# avbrd.net
KiCad netlist of a schematic drawn in Altium Designer
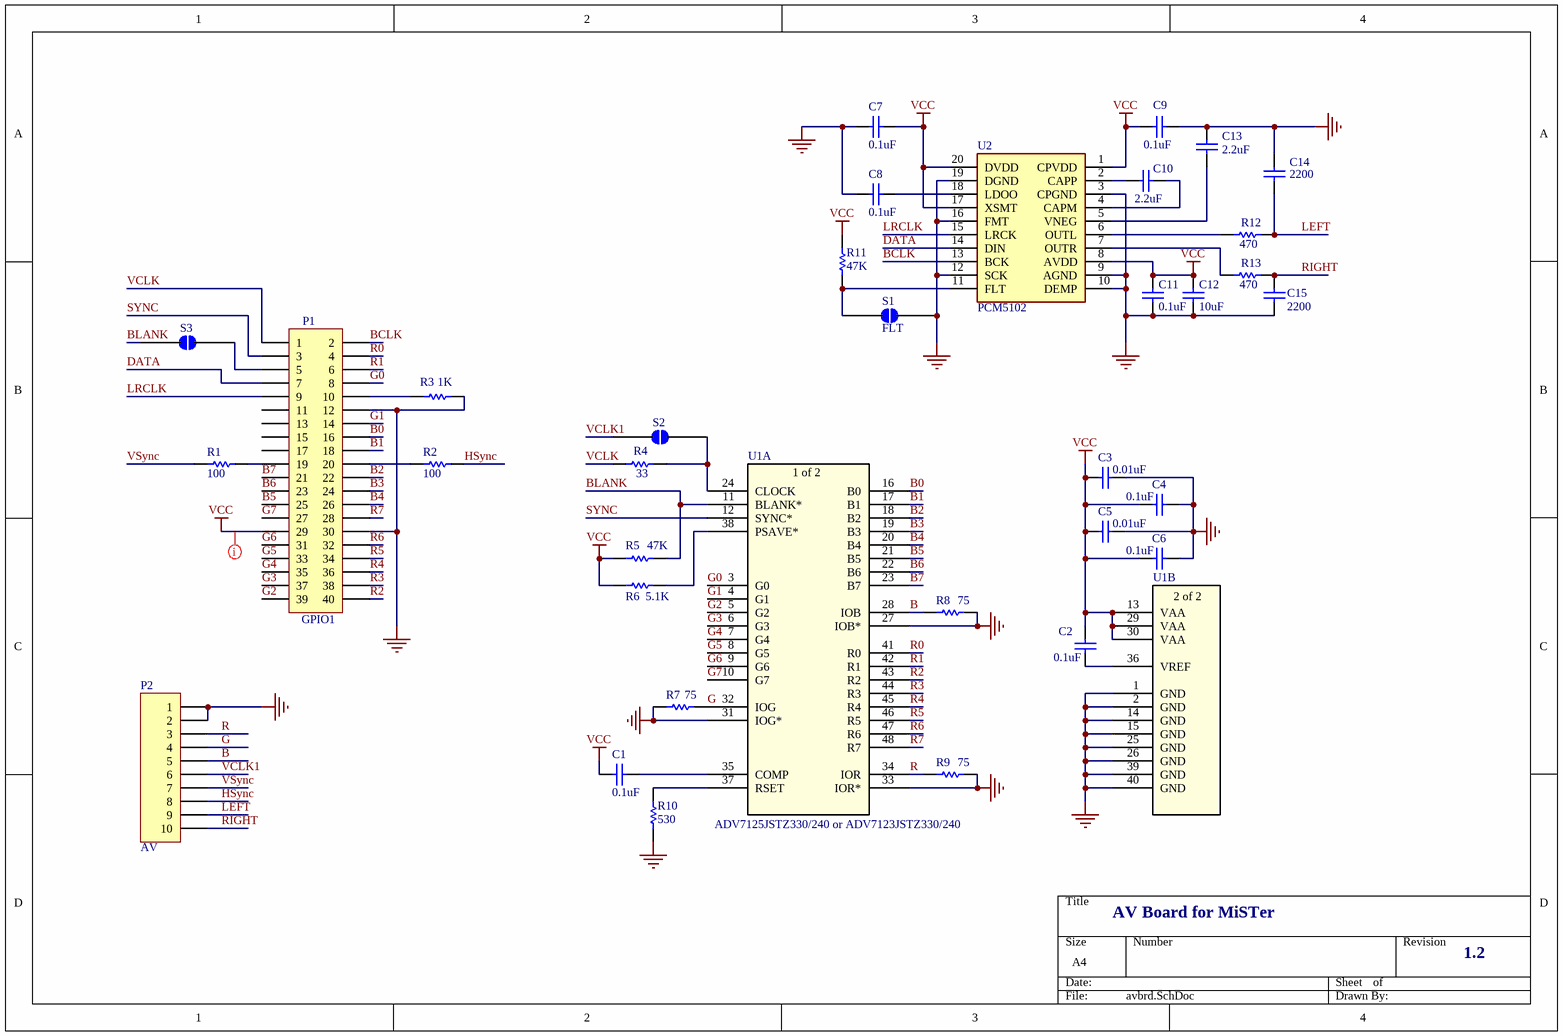
[diagram p0: avbrd.SchDoc]

(export (version "E")
  (design (tool "Eeschema 10.0.6"))
  (components
    (comp (ref "C1")
      (value "0.1uF")
      (footprint "C0805")
      (description "Ceramic Chip Capacitor - Standard")
      (fields (field (name "Comment") "C0805") (field (name "PUBLISHER") "Altium Limited"))
      (libsource (lib "lib") (part "C0805"))
    )
    (comp (ref "C2")
      (value "0.1uF")
      (footprint "C0805")
      (description "Ceramic Chip Capacitor - Standard")
      (fields (field (name "Comment") "C0805") (field (name "PUBLISHER") "Altium Limited"))
      (libsource (lib "lib") (part "C0805"))
    )
    (comp (ref "C3")
      (value "0.01uF")
      (footprint "C0805")
      (description "Ceramic Chip Capacitor - Standard")
      (fields (field (name "Comment") "C0805") (field (name "PUBLISHER") "Altium Limited"))
      (libsource (lib "lib") (part "C0805"))
    )
    (comp (ref "C4")
      (value "0.1uF")
      (footprint "C0805")
      (description "Ceramic Chip Capacitor - Standard")
      (fields (field (name "Comment") "C0805") (field (name "PUBLISHER") "Altium Limited"))
      (libsource (lib "lib") (part "C0805"))
    )
    (comp (ref "C5")
      (value "0.01uF")
      (footprint "C0805")
      (description "Ceramic Chip Capacitor - Standard")
      (fields (field (name "Comment") "C0805") (field (name "PUBLISHER") "Altium Limited"))
      (libsource (lib "lib") (part "C0805"))
    )
    (comp (ref "C6")
      (value "0.1uF")
      (footprint "C0805")
      (description "Ceramic Chip Capacitor - Standard")
      (fields (field (name "Comment") "C0805") (field (name "PUBLISHER") "Altium Limited"))
      (libsource (lib "lib") (part "C0805"))
    )
    (comp (ref "C7")
      (value "0.1uF")
      (footprint "C0805")
      (description "Ceramic Chip Capacitor - Standard")
      (fields (field (name "Comment") "C0805") (field (name "PUBLISHER") "Altium Limited"))
      (libsource (lib "lib") (part "C0805"))
    )
    (comp (ref "C8")
      (value "0.1uF")
      (footprint "C0805")
      (description "Ceramic Chip Capacitor - Standard")
      (fields (field (name "Comment") "C0805") (field (name "PUBLISHER") "Altium Limited"))
      (libsource (lib "lib") (part "C0805"))
    )
    (comp (ref "C9")
      (value "0.1uF")
      (footprint "C0805")
      (description "Ceramic Chip Capacitor - Standard")
      (fields (field (name "Comment") "C0805") (field (name "PUBLISHER") "Altium Limited"))
      (libsource (lib "lib") (part "C0805"))
    )
    (comp (ref "C10")
      (value "2.2uF")
      (footprint "C0805")
      (description "Ceramic Chip Capacitor - Standard")
      (fields (field (name "Comment") "C0805") (field (name "PUBLISHER") "Altium Limited"))
      (libsource (lib "lib") (part "C0805"))
    )
    (comp (ref "C11")
      (value "0.1uF")
      (footprint "C0805")
      (description "Ceramic Chip Capacitor - Standard")
      (fields (field (name "Comment") "C0805") (field (name "PUBLISHER") "Altium Limited"))
      (libsource (lib "lib") (part "C0805"))
    )
    (comp (ref "C12")
      (value "10uF")
      (footprint "C0805")
      (description "Ceramic Chip Capacitor - Standard")
      (fields (field (name "Comment") "C0805") (field (name "PUBLISHER") "Altium Limited"))
      (libsource (lib "lib") (part "C0805"))
    )
    (comp (ref "C13")
      (value "2.2uF")
      (footprint "C0805")
      (description "Ceramic Chip Capacitor - Standard")
      (fields (field (name "Comment") "C0805") (field (name "PUBLISHER") "Altium Limited"))
      (libsource (lib "lib") (part "C0805"))
    )
    (comp (ref "C14")
      (value "2200")
      (footprint "C0805")
      (description "Ceramic Chip Capacitor - Standard")
      (fields (field (name "Comment") "C0805") (field (name "PUBLISHER") "Altium Limited"))
      (libsource (lib "lib") (part "C0805"))
    )
    (comp (ref "C15")
      (value "2200")
      (footprint "C0805")
      (description "Ceramic Chip Capacitor - Standard")
      (fields (field (name "Comment") "C0805") (field (name "PUBLISHER") "Altium Limited"))
      (libsource (lib "lib") (part "C0805"))
    )
    (comp (ref "P1")
      (value "GPIO1")
      (footprint "HDR20x2_empty")
      (description "Header, 20-Pin, Dual row")
      (fields (field (name "PUBLISHER") "Altium Limited"))
      (libsource (lib "Miscellaneous Connectors") (part "Header 20X2"))
    )
    (comp (ref "P2")
      (value "AV")
      (footprint "HDR1X10")
      (description "Header, 10-Pin")
      (fields (field (name "PUBLISHER") "Altium Limited"))
      (libsource (lib "Miscellaneous Connectors") (part "Header 10"))
    )
    (comp (ref "R1")
      (value "100")
      (footprint "R0805")
      (fields (field (name "PUBLISHER") "Altium Limited"))
      (libsource (lib "lib") (part "R0805"))
    )
    (comp (ref "R2")
      (value "100")
      (footprint "R0805")
      (fields (field (name "PUBLISHER") "Altium Limited"))
      (libsource (lib "lib") (part "R0805"))
    )
    (comp (ref "R3")
      (value "1K")
      (footprint "R0805")
      (fields (field (name "PUBLISHER") "Altium Limited"))
      (libsource (lib "lib") (part "R0805"))
    )
    (comp (ref "R4")
      (value "33")
      (footprint "R0805")
      (fields (field (name "PUBLISHER") "Altium Limited"))
      (libsource (lib "lib") (part "R0805"))
    )
    (comp (ref "R5")
      (value "47K")
      (footprint "R0805")
      (fields (field (name "PUBLISHER") "Altium Limited"))
      (libsource (lib "lib") (part "R0805"))
    )
    (comp (ref "R6")
      (value "5.1K")
      (footprint "R0805")
      (fields (field (name "PUBLISHER") "Altium Limited"))
      (libsource (lib "lib") (part "R0805"))
    )
    (comp (ref "R7")
      (value "75")
      (footprint "R0805")
      (fields (field (name "PUBLISHER") "Altium Limited"))
      (libsource (lib "lib") (part "R0805"))
    )
    (comp (ref "R8")
      (value "75")
      (footprint "R0805")
      (fields (field (name "PUBLISHER") "Altium Limited"))
      (libsource (lib "lib") (part "R0805"))
    )
    (comp (ref "R9")
      (value "75")
      (footprint "R0805")
      (fields (field (name "PUBLISHER") "Altium Limited"))
      (libsource (lib "lib") (part "R0805"))
    )
    (comp (ref "R10")
      (value "530")
      (footprint "R0805")
      (fields (field (name "PUBLISHER") "Altium Limited"))
      (libsource (lib "lib") (part "R0805"))
    )
    (comp (ref "R11")
      (value "47K")
      (footprint "R0805")
      (fields (field (name "PUBLISHER") "Altium Limited"))
      (libsource (lib "lib") (part "R0805"))
    )
    (comp (ref "R12")
      (value "470")
      (footprint "R0805")
      (fields (field (name "PUBLISHER") "Altium Limited"))
      (libsource (lib "lib") (part "R0805"))
    )
    (comp (ref "R13")
      (value "470")
      (footprint "R0805")
      (fields (field (name "PUBLISHER") "Altium Limited"))
      (libsource (lib "lib") (part "R0805"))
    )
    (comp (ref "S1") (value "FLT") (footprint "SEL") (libsource (lib "lib") (part "SEL")))
    (comp (ref "S2") (value "~") (footprint "SEL") (libsource (lib "lib") (part "SEL")))
    (comp (ref "S3") (value "~") (footprint "SEL") (libsource (lib "lib") (part "SEL")))
    (comp (ref "U1")
      (value "ADV7125JSTZ330/240 or ADV7123JSTZ330/240")
      (footprint "ST_48_ADI")
      (fields
        (field (name "MANUFACTURER_PART_NUMBER") "ADV7125JSTZ330")
        (field (name "COPYRIGHT") "Copyright (C) 2024 Ultra Librarian. All rights reserved.")
      )
      (libsource (lib "lib") (part "ADV7125JSTZ330"))
    )
    (comp (ref "U2")
      (value "PCM5102")
      (footprint "SOP65P640X120-20N")
      (fields
        (field (name "MOUSER PART NUMBER") "595-PCM5102PW")
        (field (name "MANUFACTURER_PART_NUMBER") "PCM5102PW")
      )
      (libsource (lib "lib") (part "PCM5102"))
    )
  )
  (nets
    (net (code "1") (name "/B") (class "Default")
      (node (ref "P2") (pin "5") (pinfunction "5_5") (pintype "passive"))
      (node (ref "R8") (pin "1") (pinfunction "1_1") (pintype "passive"))
      (node (ref "U1") (pin "28") (pinfunction "IOB_28") (pintype "passive"))
    )
    (net (code "2") (name "/B0") (class "Default")
      (node (ref "P1") (pin "16") (pinfunction "16_16") (pintype "passive"))
      (node (ref "U1") (pin "16") (pinfunction "B0_16") (pintype "passive"))
    )
    (net (code "3") (name "/B1") (class "Default")
      (node (ref "P1") (pin "18") (pinfunction "18_18") (pintype "passive"))
      (node (ref "U1") (pin "17") (pinfunction "B1_17") (pintype "passive"))
    )
    (net (code "4") (name "/B2") (class "Default")
      (node (ref "P1") (pin "22") (pinfunction "22_22") (pintype "passive"))
      (node (ref "U1") (pin "18") (pinfunction "B2_18") (pintype "passive"))
    )
    (net (code "5") (name "/B3") (class "Default")
      (node (ref "P1") (pin "24") (pinfunction "24_24") (pintype "passive"))
      (node (ref "U1") (pin "19") (pinfunction "B3_19") (pintype "passive"))
    )
    (net (code "6") (name "/B4") (class "Default")
      (node (ref "P1") (pin "26") (pinfunction "26_26") (pintype "passive"))
      (node (ref "U1") (pin "20") (pinfunction "B4_20") (pintype "passive"))
    )
    (net (code "7") (name "/B5") (class "Default")
      (node (ref "P1") (pin "25") (pinfunction "25_25") (pintype "passive"))
      (node (ref "U1") (pin "21") (pinfunction "B5_21") (pintype "passive"))
    )
    (net (code "8") (name "/B6") (class "Default")
      (node (ref "P1") (pin "23") (pinfunction "23_23") (pintype "passive"))
      (node (ref "U1") (pin "22") (pinfunction "B6_22") (pintype "passive"))
    )
    (net (code "9") (name "/B7") (class "Default")
      (node (ref "P1") (pin "21") (pinfunction "21_21") (pintype "passive"))
      (node (ref "U1") (pin "23") (pinfunction "B7_23") (pintype "passive"))
    )
    (net (code "10") (name "/BCLK") (class "Default")
      (node (ref "P1") (pin "2") (pinfunction "2_2") (pintype "passive"))
      (node (ref "U2") (pin "13") (pinfunction "BCK_13") (pintype "passive"))
    )
    (net (code "11") (name "/BLANK") (class "Default")
      (node (ref "R5") (pin "1") (pinfunction "1_1") (pintype "passive"))
      (node (ref "S3") (pin "2") (pinfunction "2_2") (pintype "passive"))
      (node (ref "U1") (pin "11") (pinfunction "BLANK*_11") (pintype "passive"))
    )
    (net (code "12") (name "/DATA") (class "Default")
      (node (ref "P1") (pin "7") (pinfunction "7_7") (pintype "passive"))
      (node (ref "U2") (pin "14") (pinfunction "DIN_14") (pintype "passive"))
    )
    (net (code "13") (name "/G") (class "Default")
      (node (ref "P2") (pin "4") (pinfunction "4_4") (pintype "passive"))
      (node (ref "R7") (pin "1") (pinfunction "1_1") (pintype "passive"))
      (node (ref "U1") (pin "32") (pinfunction "IOG_32") (pintype "passive"))
    )
    (net (code "14") (name "/G0") (class "Default")
      (node (ref "P1") (pin "8") (pinfunction "8_8") (pintype "passive"))
      (node (ref "U1") (pin "3") (pinfunction "G0_3") (pintype "passive"))
    )
    (net (code "15") (name "/G1") (class "Default")
      (node (ref "P1") (pin "14") (pinfunction "14_14") (pintype "passive"))
      (node (ref "U1") (pin "4") (pinfunction "G1_4") (pintype "passive"))
    )
    (net (code "16") (name "/G2") (class "Default")
      (node (ref "P1") (pin "39") (pinfunction "39_39") (pintype "passive"))
      (node (ref "U1") (pin "5") (pinfunction "G2_5") (pintype "passive"))
    )
    (net (code "17") (name "/G3") (class "Default")
      (node (ref "P1") (pin "37") (pinfunction "37_37") (pintype "passive"))
      (node (ref "U1") (pin "6") (pinfunction "G3_6") (pintype "passive"))
    )
    (net (code "18") (name "/G4") (class "Default")
      (node (ref "P1") (pin "35") (pinfunction "35_35") (pintype "passive"))
      (node (ref "U1") (pin "7") (pinfunction "G4_7") (pintype "passive"))
    )
    (net (code "19") (name "/G5") (class "Default")
      (node (ref "P1") (pin "33") (pinfunction "33_33") (pintype "passive"))
      (node (ref "U1") (pin "8") (pinfunction "G5_8") (pintype "passive"))
    )
    (net (code "20") (name "/G6") (class "Default")
      (node (ref "P1") (pin "31") (pinfunction "31_31") (pintype "passive"))
      (node (ref "U1") (pin "9") (pinfunction "G6_9") (pintype "passive"))
    )
    (net (code "21") (name "/G7") (class "Default")
      (node (ref "P1") (pin "27") (pinfunction "27_27") (pintype "passive"))
      (node (ref "U1") (pin "10") (pinfunction "G7_10") (pintype "passive"))
    )
    (net (code "22") (name "/HSync") (class "Default")
      (node (ref "P2") (pin "8") (pinfunction "8_8") (pintype "passive"))
      (node (ref "R2") (pin "1") (pinfunction "1_1") (pintype "passive"))
    )
    (net (code "23") (name "/LEFT") (class "Default")
      (node (ref "C14") (pin "2") (pinfunction "2_2") (pintype "passive"))
      (node (ref "P2") (pin "9") (pinfunction "9_9") (pintype "passive"))
      (node (ref "R12") (pin "2") (pinfunction "2_2") (pintype "passive"))
    )
    (net (code "24") (name "/LRCLK") (class "Default")
      (node (ref "P1") (pin "9") (pinfunction "9_9") (pintype "passive"))
      (node (ref "U2") (pin "15") (pinfunction "LRCK_15") (pintype "passive"))
    )
    (net (code "25") (name "/R") (class "Default")
      (node (ref "P2") (pin "3") (pinfunction "3_3") (pintype "passive"))
      (node (ref "R9") (pin "1") (pinfunction "1_1") (pintype "passive"))
      (node (ref "U1") (pin "34") (pinfunction "IOR_34") (pintype "passive"))
    )
    (net (code "26") (name "/R0") (class "Default")
      (node (ref "P1") (pin "4") (pinfunction "4_4") (pintype "passive"))
      (node (ref "U1") (pin "41") (pinfunction "R0_41") (pintype "passive"))
    )
    (net (code "27") (name "/R1") (class "Default")
      (node (ref "P1") (pin "6") (pinfunction "6_6") (pintype "passive"))
      (node (ref "U1") (pin "42") (pinfunction "R1_42") (pintype "passive"))
    )
    (net (code "28") (name "/R2") (class "Default")
      (node (ref "P1") (pin "40") (pinfunction "40_40") (pintype "passive"))
      (node (ref "U1") (pin "43") (pinfunction "R2_43") (pintype "passive"))
    )
    (net (code "29") (name "/R3") (class "Default")
      (node (ref "P1") (pin "38") (pinfunction "38_38") (pintype "passive"))
      (node (ref "U1") (pin "44") (pinfunction "R3_44") (pintype "passive"))
    )
    (net (code "30") (name "/R4") (class "Default")
      (node (ref "P1") (pin "36") (pinfunction "36_36") (pintype "passive"))
      (node (ref "U1") (pin "45") (pinfunction "R4_45") (pintype "passive"))
    )
    (net (code "31") (name "/R5") (class "Default")
      (node (ref "P1") (pin "34") (pinfunction "34_34") (pintype "passive"))
      (node (ref "U1") (pin "46") (pinfunction "R5_46") (pintype "passive"))
    )
    (net (code "32") (name "/R6") (class "Default")
      (node (ref "P1") (pin "32") (pinfunction "32_32") (pintype "passive"))
      (node (ref "U1") (pin "47") (pinfunction "R6_47") (pintype "passive"))
    )
    (net (code "33") (name "/R7") (class "Default")
      (node (ref "P1") (pin "28") (pinfunction "28_28") (pintype "passive"))
      (node (ref "U1") (pin "48") (pinfunction "R7_48") (pintype "passive"))
    )
    (net (code "34") (name "/RIGHT") (class "Default")
      (node (ref "C15") (pin "1") (pinfunction "1_1") (pintype "passive"))
      (node (ref "P2") (pin "10") (pinfunction "10_10") (pintype "passive"))
      (node (ref "R13") (pin "2") (pinfunction "2_2") (pintype "passive"))
    )
    (net (code "35") (name "/SYNC") (class "Default")
      (node (ref "P1") (pin "3") (pinfunction "3_3") (pintype "passive"))
      (node (ref "U1") (pin "12") (pinfunction "SYNC*_12") (pintype "passive"))
    )
    (net (code "36") (name "/VCLK") (class "Default")
      (node (ref "P1") (pin "1") (pinfunction "1_1") (pintype "passive"))
      (node (ref "R4") (pin "2") (pinfunction "2_2") (pintype "passive"))
    )
    (net (code "37") (name "/VCLK1") (class "Default")
      (node (ref "P2") (pin "6") (pinfunction "6_6") (pintype "passive"))
      (node (ref "S2") (pin "2") (pinfunction "2_2") (pintype "passive"))
    )
    (net (code "38") (name "/VSync") (class "Default")
      (node (ref "P2") (pin "7") (pinfunction "7_7") (pintype "passive"))
      (node (ref "R1") (pin "1") (pinfunction "1_1") (pintype "passive"))
    )
    (net (code "39") (name "GND") (class "Default")
      (node (ref "C11") (pin "1") (pinfunction "1_1") (pintype "passive"))
      (node (ref "C12") (pin "1") (pinfunction "1_1") (pintype "passive"))
      (node (ref "C13") (pin "2") (pinfunction "2_2") (pintype "passive"))
      (node (ref "C14") (pin "1") (pinfunction "1_1") (pintype "passive"))
      (node (ref "C15") (pin "2") (pinfunction "2_2") (pintype "passive"))
      (node (ref "C3") (pin "1") (pinfunction "1_1") (pintype "passive"))
      (node (ref "C4") (pin "1") (pinfunction "1_1") (pintype "passive"))
      (node (ref "C5") (pin "1") (pinfunction "1_1") (pintype "passive"))
      (node (ref "C6") (pin "1") (pinfunction "1_1") (pintype "passive"))
      (node (ref "C7") (pin "1") (pinfunction "1_1") (pintype "passive"))
      (node (ref "C8") (pin "1") (pinfunction "1_1") (pintype "passive"))
      (node (ref "C9") (pin "2") (pinfunction "2_2") (pintype "passive"))
      (node (ref "P1") (pin "12") (pinfunction "12_12") (pintype "passive"))
      (node (ref "P1") (pin "30") (pinfunction "30_30") (pintype "passive"))
      (node (ref "P2") (pin "1") (pinfunction "1_1") (pintype "passive"))
      (node (ref "P2") (pin "2") (pinfunction "2_2") (pintype "passive"))
      (node (ref "R10") (pin "1") (pinfunction "1_1") (pintype "passive"))
      (node (ref "R3") (pin "1") (pinfunction "1_1") (pintype "passive"))
      (node (ref "R7") (pin "2") (pinfunction "2_2") (pintype "passive"))
      (node (ref "R8") (pin "2") (pinfunction "2_2") (pintype "passive"))
      (node (ref "R9") (pin "2") (pinfunction "2_2") (pintype "passive"))
      (node (ref "S1") (pin "2") (pinfunction "2_2") (pintype "passive"))
      (node (ref "U1") (pin "1") (pinfunction "GND_1") (pintype "passive"))
      (node (ref "U1") (pin "14") (pinfunction "GND_14") (pintype "passive"))
      (node (ref "U1") (pin "15") (pinfunction "GND_15") (pintype "passive"))
      (node (ref "U1") (pin "2") (pinfunction "GND_2") (pintype "passive"))
      (node (ref "U1") (pin "25") (pinfunction "GND_25") (pintype "passive"))
      (node (ref "U1") (pin "26") (pinfunction "GND_26") (pintype "passive"))
      (node (ref "U1") (pin "27") (pinfunction "IOB*_27") (pintype "passive"))
      (node (ref "U1") (pin "31") (pinfunction "IOG*_31") (pintype "passive"))
      (node (ref "U1") (pin "33") (pinfunction "IOR*_33") (pintype "passive"))
      (node (ref "U1") (pin "39") (pinfunction "GND_39") (pintype "passive"))
      (node (ref "U1") (pin "40") (pinfunction "GND_40") (pintype "passive"))
      (node (ref "U2") (pin "10") (pinfunction "DEMP_10") (pintype "passive"))
      (node (ref "U2") (pin "12") (pinfunction "SCK_12") (pintype "passive"))
      (node (ref "U2") (pin "16") (pinfunction "FMT_16") (pintype "passive"))
      (node (ref "U2") (pin "19") (pinfunction "DGND_19") (pintype "passive"))
      (node (ref "U2") (pin "3") (pinfunction "CPGND_3") (pintype "passive"))
      (node (ref "U2") (pin "9") (pinfunction "AGND_9") (pintype "passive"))
    )
    (net (code "40") (name "Net-(P1-Pad5)") (class "Default")
      (node (ref "P1") (pin "5") (pinfunction "5_5") (pintype "passive"))
      (node (ref "S3") (pin "1") (pinfunction "1_1") (pintype "passive"))
    )
    (net (code "41") (name "Net-(P1-Pad10)") (class "Default")
      (node (ref "P1") (pin "10") (pinfunction "10_10") (pintype "passive"))
      (node (ref "R3") (pin "2") (pinfunction "2_2") (pintype "passive"))
    )
    (net (code "42") (name "Net-(P1-Pad19)") (class "Default")
      (node (ref "P1") (pin "19") (pinfunction "19_19") (pintype "passive"))
      (node (ref "R1") (pin "2") (pinfunction "2_2") (pintype "passive"))
    )
    (net (code "43") (name "Net-(P1-Pad20)") (class "Default")
      (node (ref "P1") (pin "20") (pinfunction "20_20") (pintype "passive"))
      (node (ref "R2") (pin "2") (pinfunction "2_2") (pintype "passive"))
    )
    (net (code "44") (name "Net-(U1A-CLOCK)") (class "Default")
      (node (ref "R4") (pin "1") (pinfunction "1_1") (pintype "passive"))
      (node (ref "S2") (pin "1") (pinfunction "1_1") (pintype "passive"))
      (node (ref "U1") (pin "24") (pinfunction "CLOCK_24") (pintype "passive"))
    )
    (net (code "45") (name "Net-(U1A-COMP)") (class "Default")
      (node (ref "C1") (pin "1") (pinfunction "1_1") (pintype "passive"))
      (node (ref "U1") (pin "35") (pinfunction "COMP_35") (pintype "passive"))
    )
    (net (code "46") (name "Net-(U1A-PSAVE*)") (class "Default")
      (node (ref "R6") (pin "1") (pinfunction "1_1") (pintype "passive"))
      (node (ref "U1") (pin "38") (pinfunction "PSAVE*_38") (pintype "passive"))
    )
    (net (code "47") (name "Net-(U1A-RSET)") (class "Default")
      (node (ref "R10") (pin "2") (pinfunction "2_2") (pintype "passive"))
      (node (ref "U1") (pin "37") (pinfunction "RSET_37") (pintype "passive"))
    )
    (net (code "48") (name "Net-(U1B-VREF)") (class "Default")
      (node (ref "C2") (pin "2") (pinfunction "2_2") (pintype "passive"))
      (node (ref "U1") (pin "36") (pinfunction "VREF_36") (pintype "passive"))
    )
    (net (code "49") (name "Net-(U2-CAPM)") (class "Default")
      (node (ref "C10") (pin "1") (pinfunction "1_1") (pintype "passive"))
      (node (ref "U2") (pin "4") (pinfunction "CAPM_4") (pintype "passive"))
    )
    (net (code "50") (name "Net-(U2-CAPP)") (class "Default")
      (node (ref "C10") (pin "2") (pinfunction "2_2") (pintype "passive"))
      (node (ref "U2") (pin "2") (pinfunction "CAPP_2") (pintype "passive"))
    )
    (net (code "51") (name "Net-(U2-FLT)") (class "Default")
      (node (ref "R11") (pin "1") (pinfunction "1_1") (pintype "passive"))
      (node (ref "S1") (pin "1") (pinfunction "1_1") (pintype "passive"))
      (node (ref "U2") (pin "11") (pinfunction "FLT_11") (pintype "passive"))
    )
    (net (code "52") (name "Net-(U2-LDOO)") (class "Default")
      (node (ref "C8") (pin "2") (pinfunction "2_2") (pintype "passive"))
      (node (ref "U2") (pin "18") (pinfunction "LDOO_18") (pintype "passive"))
    )
    (net (code "53") (name "Net-(U2-OUTL)") (class "Default")
      (node (ref "R12") (pin "1") (pinfunction "1_1") (pintype "passive"))
      (node (ref "U2") (pin "6") (pinfunction "OUTL_6") (pintype "passive"))
    )
    (net (code "54") (name "Net-(U2-OUTR)") (class "Default")
      (node (ref "R13") (pin "1") (pinfunction "1_1") (pintype "passive"))
      (node (ref "U2") (pin "7") (pinfunction "OUTR_7") (pintype "passive"))
    )
    (net (code "55") (name "Net-(U2-VNEG)") (class "Default")
      (node (ref "C13") (pin "1") (pinfunction "1_1") (pintype "passive"))
      (node (ref "U2") (pin "5") (pinfunction "VNEG_5") (pintype "passive"))
    )
    (net (code "56") (name "VCC") (class "Default")
      (node (ref "C1") (pin "2") (pinfunction "2_2") (pintype "passive"))
      (node (ref "C11") (pin "2") (pinfunction "2_2") (pintype "passive"))
      (node (ref "C12") (pin "2") (pinfunction "2_2") (pintype "passive"))
      (node (ref "C2") (pin "1") (pinfunction "1_1") (pintype "passive"))
      (node (ref "C3") (pin "2") (pinfunction "2_2") (pintype "passive"))
      (node (ref "C4") (pin "2") (pinfunction "2_2") (pintype "passive"))
      (node (ref "C5") (pin "2") (pinfunction "2_2") (pintype "passive"))
      (node (ref "C6") (pin "2") (pinfunction "2_2") (pintype "passive"))
      (node (ref "C7") (pin "2") (pinfunction "2_2") (pintype "passive"))
      (node (ref "C9") (pin "1") (pinfunction "1_1") (pintype "passive"))
      (node (ref "P1") (pin "29") (pinfunction "29_29") (pintype "passive"))
      (node (ref "R11") (pin "2") (pinfunction "2_2") (pintype "passive"))
      (node (ref "R5") (pin "2") (pinfunction "2_2") (pintype "passive"))
      (node (ref "R6") (pin "2") (pinfunction "2_2") (pintype "passive"))
      (node (ref "U1") (pin "13") (pinfunction "VAA_13") (pintype "power_in"))
      (node (ref "U1") (pin "29") (pinfunction "VAA_29") (pintype "power_in"))
      (node (ref "U1") (pin "30") (pinfunction "VAA_30") (pintype "power_in"))
      (node (ref "U2") (pin "1") (pinfunction "CPVDD_1") (pintype "passive"))
      (node (ref "U2") (pin "17") (pinfunction "XSMT_17") (pintype "passive"))
      (node (ref "U2") (pin "20") (pinfunction "DVDD_20") (pintype "passive"))
      (node (ref "U2") (pin "8") (pinfunction "AVDD_8") (pintype "passive"))
    )
    (net (code "57") (name "unconnected-(P1-Pad11)") (class "Default")
      (node (ref "P1") (pin "11") (pinfunction "11_11") (pintype "passive"))
    )
    (net (code "58") (name "unconnected-(P1-Pad13)") (class "Default")
      (node (ref "P1") (pin "13") (pinfunction "13_13") (pintype "passive"))
    )
    (net (code "59") (name "unconnected-(P1-Pad15)") (class "Default")
      (node (ref "P1") (pin "15") (pinfunction "15_15") (pintype "passive"))
    )
    (net (code "60") (name "unconnected-(P1-Pad17)") (class "Default")
      (node (ref "P1") (pin "17") (pinfunction "17_17") (pintype "passive"))
    )
  )
)
